# I2C_Multiplexer.net
KiCad netlist of a schematic drawn in Altium Designer
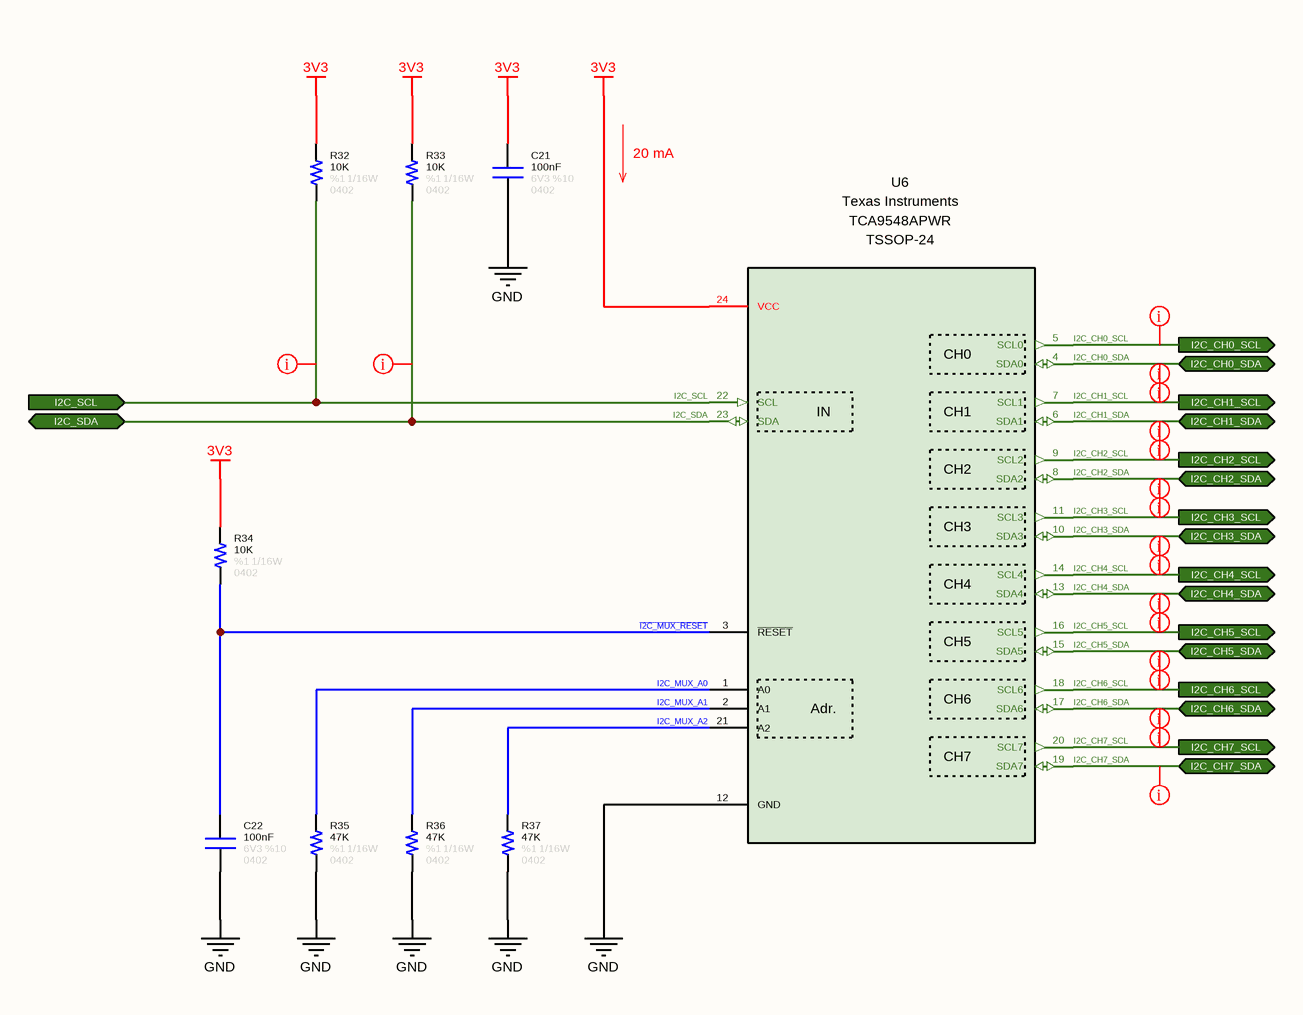
[diagram p0: I2C Multiplexer.SchDoc]

(export (version "E")
  (design (tool "Eeschema 10.0.6"))
  (components
    (comp (ref "C21")
      (value "100nF")
      (footprint "CAPACITOR_0402")
      (description "Capacitor - 100nF [0402-6V3] (Ceramic)")
      (fields
        (field (name "MANUFACTURER PART NUMBER") "04026D104KAT4A")
        (field (name "TOLERANCE") "%10")
        (field (name "VOLTAGE") "6V3")
        (field (name "CASE") "0402")
        (field (name "Comment") "Capacitor - 100nF [0402] (Ceramic)")
      )
      (libsource (lib "Akkoyun") (part "Capacitor - 100nF [0402-6V3]"))
    )
    (comp (ref "C22")
      (value "100nF")
      (footprint "CAPACITOR_0402")
      (description "Capacitor - 100nF [0402-6V3] (Ceramic)")
      (fields
        (field (name "MANUFACTURER PART NUMBER") "04026D104KAT4A")
        (field (name "TOLERANCE") "%10")
        (field (name "VOLTAGE") "6V3")
        (field (name "CASE") "0402")
        (field (name "Comment") "Capacitor - 100nF [0402] (Ceramic)")
      )
      (libsource (lib "Akkoyun") (part "Capacitor - 100nF [0402-6V3]"))
    )
    (comp (ref "R32")
      (value "10K")
      (footprint "RESISTOR_0402")
      (description "Thick Film Resistors - SMD 1/16 W 10 KOhm 1%")
      (fields
        (field (name "MANUFACTURER PART NUMBER") "CRCW040210K0FKED")
        (field (name "TOLERANCE") "%1")
        (field (name "CASE") "0402")
        (field (name "POWER") "1/16W")
        (field (name "Comment") "10K - 0402 - %1 - 1/16W")
      )
      (libsource (lib "Akkoyun") (part "Resistor - 10K [0402]"))
    )
    (comp (ref "R33")
      (value "10K")
      (footprint "RESISTOR_0402")
      (description "Thick Film Resistors - SMD 1/16 W 10 KOhm 1%")
      (fields
        (field (name "MANUFACTURER PART NUMBER") "CRCW040210K0FKED")
        (field (name "TOLERANCE") "%1")
        (field (name "CASE") "0402")
        (field (name "POWER") "1/16W")
        (field (name "Comment") "10K - 0402 - %1 - 1/16W")
      )
      (libsource (lib "Akkoyun") (part "Resistor - 10K [0402]"))
    )
    (comp (ref "R34")
      (value "10K")
      (footprint "RESISTOR_0402")
      (description "Thick Film Resistors - SMD 1/16 W 10 KOhm 1%")
      (fields
        (field (name "MANUFACTURER PART NUMBER") "CRCW040210K0FKED")
        (field (name "TOLERANCE") "%1")
        (field (name "CASE") "0402")
        (field (name "POWER") "1/16W")
        (field (name "Comment") "10K - 0402 - %1 - 1/16W")
      )
      (libsource (lib "Akkoyun") (part "Resistor - 10K [0402]"))
    )
    (comp (ref "R35")
      (value "47K")
      (footprint "RESISTOR_0402")
      (description "Thick Film Resistors - SMD 1/16 W 47 KOhm 1%")
      (fields
        (field (name "MANUFACTURER PART NUMBER") "CRCW040247K0FKED")
        (field (name "TOLERANCE") "%1")
        (field (name "CASE") "0402")
        (field (name "POWER") "1/16W")
        (field (name "Comment") "47K - 0402 - %1 - 1/16W")
      )
      (libsource (lib "Akkoyun") (part "Resistor - 47K [0402]"))
    )
    (comp (ref "R36")
      (value "47K")
      (footprint "RESISTOR_0402")
      (description "Thick Film Resistors - SMD 1/16 W 47 KOhm 1%")
      (fields
        (field (name "MANUFACTURER PART NUMBER") "CRCW040247K0FKED")
        (field (name "TOLERANCE") "%1")
        (field (name "CASE") "0402")
        (field (name "POWER") "1/16W")
        (field (name "Comment") "47K - 0402 - %1 - 1/16W")
      )
      (libsource (lib "Akkoyun") (part "Resistor - 47K [0402]"))
    )
    (comp (ref "R37")
      (value "47K")
      (footprint "RESISTOR_0402")
      (description "Thick Film Resistors - SMD 1/16 W 47 KOhm 1%")
      (fields
        (field (name "MANUFACTURER PART NUMBER") "CRCW040247K0FKED")
        (field (name "TOLERANCE") "%1")
        (field (name "CASE") "0402")
        (field (name "POWER") "1/16W")
        (field (name "Comment") "47K - 0402 - %1 - 1/16W")
      )
      (libsource (lib "Akkoyun") (part "Resistor - 47K [0402]"))
    )
    (comp (ref "U6")
      (value "TCA9548APWR")
      (footprint "TSSOP-24")
      (description "TEXAS INSTRUMENTS - TCA9548APWR - I2C SWITCH W/ RESET, 8-CH, TSSOP-24")
      (fields
        (field (name "MANUFACTURER NAME") "Texas Instruments")
        (field (name "MANUFACTURER PART NUMBER") "TCA9548APWR")
        (field (name "CASE") "TSSOP-24")
      )
      (libsource (lib "Akkoyun") (part "IC - TCA9548"))
    )
  )
  (nets
    (net (code "1") (name "/I2C_CH0_SCL") (class "Default")
      (node (ref "U6") (pin "5") (pinfunction "SCL0_5") (pintype "output"))
    )
    (net (code "2") (name "/I2C_CH0_SDA") (class "Default")
      (node (ref "U6") (pin "4") (pinfunction "SDA0_4") (pintype "bidirectional"))
    )
    (net (code "3") (name "/I2C_CH1_SCL") (class "Default")
      (node (ref "U6") (pin "7") (pinfunction "SCL1_7") (pintype "output"))
    )
    (net (code "4") (name "/I2C_CH1_SDA") (class "Default")
      (node (ref "U6") (pin "6") (pinfunction "SDA1_6") (pintype "bidirectional"))
    )
    (net (code "5") (name "/I2C_CH2_SCL") (class "Default")
      (node (ref "U6") (pin "9") (pinfunction "SCL2_9") (pintype "output"))
    )
    (net (code "6") (name "/I2C_CH2_SDA") (class "Default")
      (node (ref "U6") (pin "8") (pinfunction "SDA2_8") (pintype "bidirectional"))
    )
    (net (code "7") (name "/I2C_CH3_SCL") (class "Default")
      (node (ref "U6") (pin "11") (pinfunction "SCL3_11") (pintype "output"))
    )
    (net (code "8") (name "/I2C_CH3_SDA") (class "Default")
      (node (ref "U6") (pin "10") (pinfunction "SDA3_10") (pintype "bidirectional"))
    )
    (net (code "9") (name "/I2C_CH4_SCL") (class "Default")
      (node (ref "U6") (pin "14") (pinfunction "SCL4_14") (pintype "output"))
    )
    (net (code "10") (name "/I2C_CH4_SDA") (class "Default")
      (node (ref "U6") (pin "13") (pinfunction "SDA4_13") (pintype "bidirectional"))
    )
    (net (code "11") (name "/I2C_CH5_SCL") (class "Default")
      (node (ref "U6") (pin "16") (pinfunction "SCL5_16") (pintype "output"))
    )
    (net (code "12") (name "/I2C_CH5_SDA") (class "Default")
      (node (ref "U6") (pin "15") (pinfunction "SDA5_15") (pintype "bidirectional"))
    )
    (net (code "13") (name "/I2C_CH6_SCL") (class "Default")
      (node (ref "U6") (pin "18") (pinfunction "SCL6_18") (pintype "output"))
    )
    (net (code "14") (name "/I2C_CH6_SDA") (class "Default")
      (node (ref "U6") (pin "17") (pinfunction "SDA6_17") (pintype "bidirectional"))
    )
    (net (code "15") (name "/I2C_CH7_SCL") (class "Default")
      (node (ref "U6") (pin "20") (pinfunction "SCL7_20") (pintype "output"))
    )
    (net (code "16") (name "/I2C_CH7_SDA") (class "Default")
      (node (ref "U6") (pin "19") (pinfunction "SDA7_19") (pintype "bidirectional"))
    )
    (net (code "17") (name "/I2C_MUX_A0") (class "Default")
      (node (ref "R35") (pin "2") (pinfunction "2_2") (pintype "passive"))
      (node (ref "U6") (pin "1") (pinfunction "A0_1") (pintype "passive"))
    )
    (net (code "18") (name "/I2C_MUX_A1") (class "Default")
      (node (ref "R36") (pin "2") (pinfunction "2_2") (pintype "passive"))
      (node (ref "U6") (pin "2") (pinfunction "A1_2") (pintype "passive"))
    )
    (net (code "19") (name "/I2C_MUX_A2") (class "Default")
      (node (ref "R37") (pin "2") (pinfunction "2_2") (pintype "passive"))
      (node (ref "U6") (pin "21") (pinfunction "A2_21") (pintype "passive"))
    )
    (net (code "20") (name "/I2C_SCL") (class "Default")
      (node (ref "R32") (pin "1") (pinfunction "1_1") (pintype "passive"))
      (node (ref "U6") (pin "22") (pinfunction "SCL_22") (pintype "input"))
    )
    (net (code "21") (name "/I2C_SDA") (class "Default")
      (node (ref "R33") (pin "1") (pinfunction "1_1") (pintype "passive"))
      (node (ref "U6") (pin "23") (pinfunction "SDA_23") (pintype "bidirectional"))
    )
    (net (code "22") (name "/~{I2C_MUX_RESET}") (class "Default")
      (node (ref "C22") (pin "2") (pinfunction "2_2") (pintype "passive"))
      (node (ref "R34") (pin "1") (pinfunction "1_1") (pintype "passive"))
      (node (ref "U6") (pin "3") (pinfunction "~{RESET}_3") (pintype "power_in"))
    )
    (net (code "23") (name "3V3") (class "Default")
      (node (ref "C21") (pin "2") (pinfunction "2_2") (pintype "passive"))
      (node (ref "R32") (pin "2") (pinfunction "2_2") (pintype "passive"))
      (node (ref "R33") (pin "2") (pinfunction "2_2") (pintype "passive"))
      (node (ref "R34") (pin "2") (pinfunction "2_2") (pintype "passive"))
      (node (ref "U6") (pin "24") (pinfunction "VCC_24") (pintype "power_in"))
    )
    (net (code "24") (name "GND") (class "Default")
      (node (ref "C21") (pin "1") (pinfunction "1_1") (pintype "passive"))
      (node (ref "C22") (pin "1") (pinfunction "1_1") (pintype "passive"))
      (node (ref "R35") (pin "1") (pinfunction "1_1") (pintype "passive"))
      (node (ref "R36") (pin "1") (pinfunction "1_1") (pintype "passive"))
      (node (ref "R37") (pin "1") (pinfunction "1_1") (pintype "passive"))
      (node (ref "U6") (pin "12") (pinfunction "GND_12") (pintype "power_in"))
    )
  )
)
